# BoostRegulator.net
KiCad netlist of a schematic drawn in Altium Designer
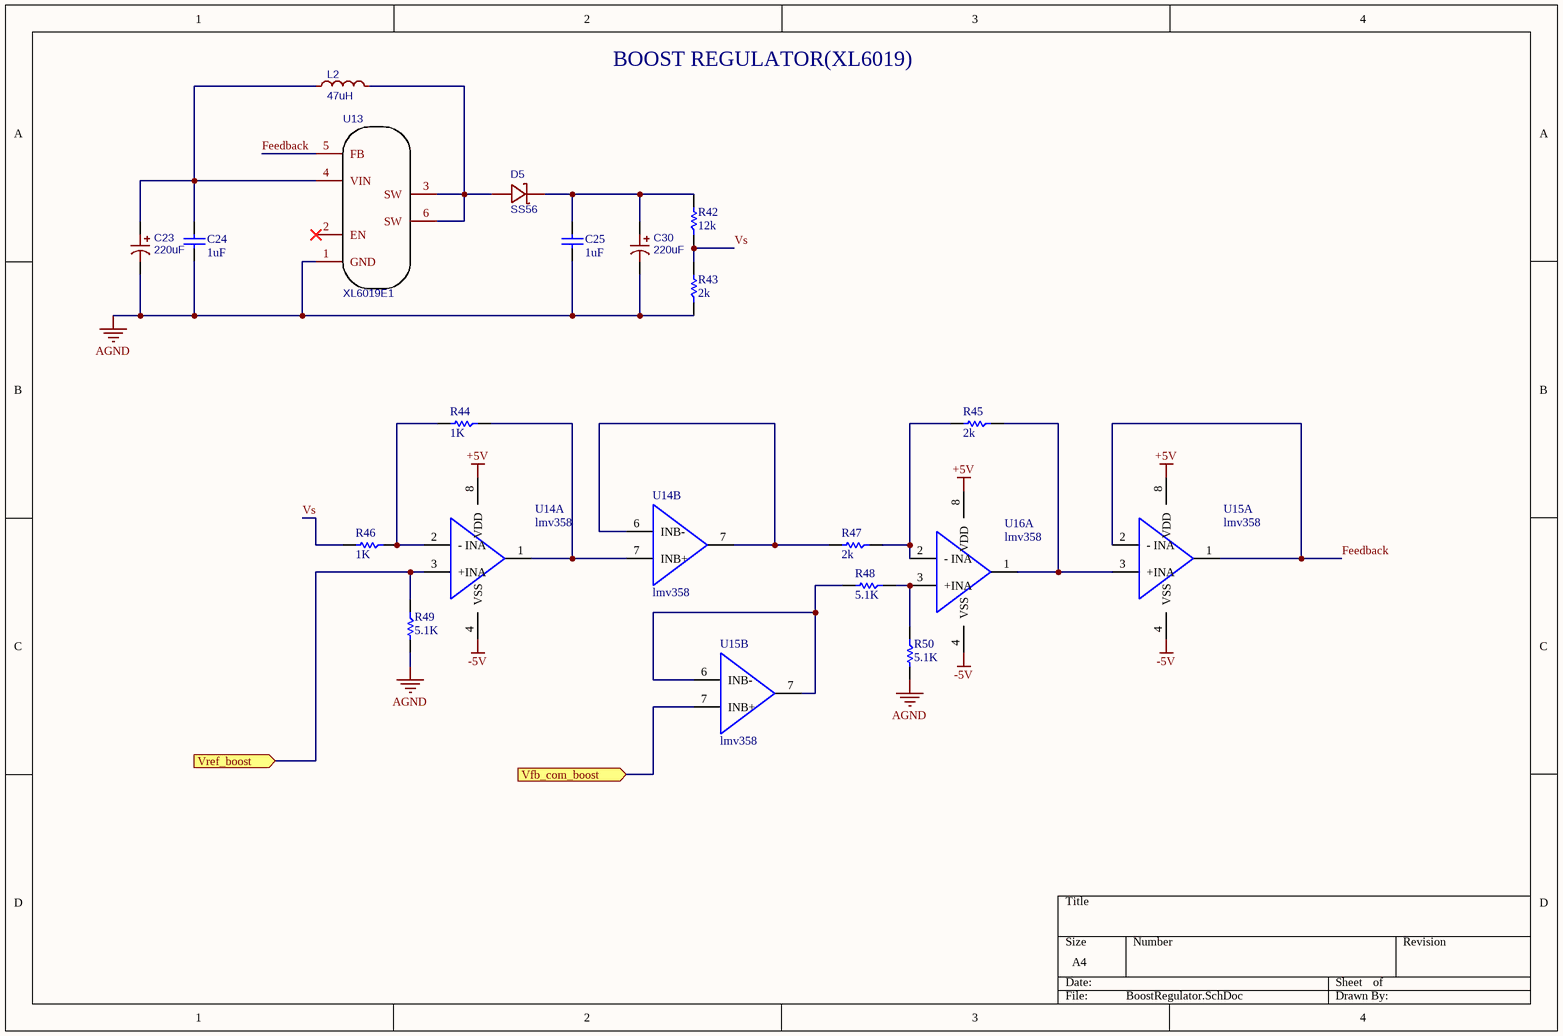
[diagram p0: BoostRegulator.SchDoc]

(export (version "E")
  (design (tool "Eeschema 10.0.6"))
  (components
    (comp (ref "C23")
      (value "220uF")
      (footprint "CAP-SMD_BD10.0-L10.3-W10.3-LS11.0-FD")
      (fields
        (field (name "BOM_SUPPLIER PART") "C2887271")
        (field (name "BOM_MANUFACTURER PART") "RVT220UF50V67RV0021")
        (field (name "CONTRIBUTOR") "LCSC")
      )
      (libsource (lib "Portable power supply") (part "220uF"))
    )
    (comp (ref "C24")
      (value "1uF")
      (footprint "0805C")
      (description "Capacitor")
      (fields (field (name "REVIEWED BY") "RM - 2018/08/05"))
      (libsource (lib "Portable power supply") (part "C_1uf"))
    )
    (comp (ref "C25")
      (value "1uF")
      (footprint "0805C")
      (description "Capacitor")
      (fields (field (name "REVIEWED BY") "RM - 2018/08/05"))
      (libsource (lib "Portable power supply") (part "C_1uf"))
    )
    (comp (ref "C30")
      (value "220uF")
      (footprint "CAP-SMD_BD10.0-L10.3-W10.3-LS11.0-FD")
      (fields
        (field (name "BOM_SUPPLIER PART") "C2887271")
        (field (name "BOM_MANUFACTURER PART") "RVT220UF50V67RV0021")
        (field (name "CONTRIBUTOR") "LCSC")
      )
      (libsource (lib "Portable power supply") (part "220uF"))
    )
    (comp (ref "D5")
      (value "SS56")
      (footprint "SMA_L4.3-W2.6-LS5.2-RD")
      (fields (field (name "BOM_SUPPLIER PART") "C65009"))
      (libsource (lib "Portable power supply") (part "SS56"))
    )
    (comp (ref "L2")
      (value "47uH")
      (footprint "IND-SMD_L12.6-W12.6_MCF-13XX")
      (fields
        (field (name "BOM_SUPPLIER PART") "C497913")
        (field (name "BOM_MANUFACTURER PART") "YSPI1365-470M")
        (field (name "CONTRIBUTOR") "LCSC")
      )
      (libsource (lib "Portable power supply") (part "47uH"))
    )
    (comp (ref "R42")
      (value "12k")
      (footprint "0805")
      (description "Resistor")
      (fields (field (name "REVIEWED BY") "RM - 2018/08/05"))
      (libsource (lib "Portable power supply") (part "R_12k"))
    )
    (comp (ref "R43")
      (value "2k")
      (footprint "0805")
      (description "Resistor")
      (fields (field (name "REVIEWED BY") "RM - 2018/08/05"))
      (libsource (lib "Portable power supply") (part "R_2k"))
    )
    (comp (ref "R44")
      (value "1K")
      (footprint "0805")
      (description "Resistor")
      (fields (field (name "REVIEWED BY") "RM - 2018/08/05"))
      (libsource (lib "Portable power supply") (part "R_6"))
    )
    (comp (ref "R45")
      (value "2k")
      (footprint "0805")
      (description "Resistor")
      (fields (field (name "REVIEWED BY") "RM - 2018/08/05"))
      (libsource (lib "Portable power supply") (part "R_3"))
    )
    (comp (ref "R46")
      (value "1K")
      (footprint "0805")
      (description "Resistor")
      (fields (field (name "REVIEWED BY") "RM - 2018/08/05"))
      (libsource (lib "Portable power supply") (part "R_6"))
    )
    (comp (ref "R47")
      (value "2k")
      (footprint "0805")
      (description "Resistor")
      (fields (field (name "REVIEWED BY") "RM - 2018/08/05"))
      (libsource (lib "Portable power supply") (part "R_3"))
    )
    (comp (ref "R48")
      (value "5.1K")
      (footprint "0805")
      (description "Resistor")
      (fields (field (name "REVIEWED BY") "RM - 2018/08/05"))
      (libsource (lib "Portable power supply") (part "R_1"))
    )
    (comp (ref "R49")
      (value "5.1K")
      (footprint "0805")
      (description "Resistor")
      (fields (field (name "REVIEWED BY") "RM - 2018/08/05"))
      (libsource (lib "Portable power supply") (part "R_1"))
    )
    (comp (ref "R50")
      (value "5.1K")
      (footprint "0805")
      (description "Resistor")
      (fields (field (name "REVIEWED BY") "RM - 2018/08/05"))
      (libsource (lib "Portable power supply") (part "R_1"))
    )
    (comp (ref "U13")
      (value "XL6019E1")
      (footprint "TO-263-5_L10.2-W9.9-P1.70-LS14.4-TL")
      (fields (field (name "BOM_SUPPLIER PART") "C73018"))
      (libsource (lib "Portable power supply") (part "XL6019E1"))
    )
    (comp (ref "U14")
      (value "lmv358")
      (footprint "SOP-8_L4.9-W3.9-P1.27-LS6.0-BL")
      (description "OpAmp High Frequency Dual")
      (fields (field (name "REVIEWED BY") "RM - 2018/08/05"))
      (libsource (lib "Portable power supply") (part "LMV358-SR"))
    )
    (comp (ref "U15")
      (value "lmv358")
      (footprint "SOP-8_L4.9-W3.9-P1.27-LS6.0-BL")
      (description "OpAmp High Frequency Dual")
      (fields (field (name "REVIEWED BY") "RM - 2018/08/05"))
      (libsource (lib "Portable power supply") (part "LMV358-SR"))
    )
    (comp (ref "U16")
      (value "lmv358")
      (footprint "SOP-8_L4.9-W3.9-P1.27-LS6.0-BL")
      (description "OpAmp High Frequency Dual")
      (fields (field (name "REVIEWED BY") "RM - 2018/08/05"))
      (libsource (lib "Portable power supply") (part "LMV358-SR"))
    )
  )
  (nets
    (net (code "1") (name "+5V") (class "Default")
      (node (ref "U14") (pin "8") (pinfunction "VDD_8") (pintype "passive"))
      (node (ref "U15") (pin "8") (pinfunction "VDD_8") (pintype "passive"))
      (node (ref "U16") (pin "8") (pinfunction "VDD_8") (pintype "passive"))
    )
    (net (code "2") (name "-5V") (class "Default")
      (node (ref "U14") (pin "4") (pinfunction "VSS_4") (pintype "passive"))
      (node (ref "U15") (pin "4") (pinfunction "VSS_4") (pintype "passive"))
      (node (ref "U16") (pin "4") (pinfunction "VSS_4") (pintype "passive"))
    )
    (net (code "3") (name "/Feedback") (class "Default")
      (node (ref "U13") (pin "5") (pinfunction "FB_5") (pintype "passive"))
      (node (ref "U15") (pin "1") (pinfunction "OUTA_1") (pintype "passive"))
      (node (ref "U15") (pin "2") (pinfunction "-_INA_2") (pintype "passive"))
    )
    (net (code "4") (name "/Vfb_com_boost") (class "Default")
      (node (ref "U15") (pin "7") (pinfunction "INB+_7") (pintype "passive"))
    )
    (net (code "5") (name "/Vref_boost") (class "Default")
      (node (ref "R49") (pin "1") (pintype "passive"))
      (node (ref "U14") (pin "3") (pinfunction "+INA_3") (pintype "passive"))
    )
    (net (code "6") (name "/Vs") (class "Default")
      (node (ref "R42") (pin "1") (pintype "passive"))
      (node (ref "R43") (pin "2") (pintype "passive"))
      (node (ref "R46") (pin "2") (pintype "passive"))
    )
    (net (code "7") (name "AGND") (class "Default")
      (node (ref "C23") (pin "2") (pinfunction "2_2") (pintype "passive"))
      (node (ref "C24") (pin "2") (pinfunction "2_2") (pintype "passive"))
      (node (ref "C25") (pin "2") (pinfunction "2_2") (pintype "passive"))
      (node (ref "C30") (pin "2") (pinfunction "2_2") (pintype "passive"))
      (node (ref "R43") (pin "1") (pintype "passive"))
      (node (ref "R49") (pin "2") (pintype "passive"))
      (node (ref "R50") (pin "2") (pintype "passive"))
      (node (ref "U13") (pin "1") (pinfunction "GND_1") (pintype "passive"))
    )
    (net (code "8") (name "Net-(D5-A)") (class "Default")
      (node (ref "D5") (pin "2") (pinfunction "A_2") (pintype "passive"))
      (node (ref "L2") (pin "2") (pinfunction "2_2") (pintype "passive"))
      (node (ref "U13") (pin "3") (pinfunction "SW_3") (pintype "passive"))
      (node (ref "U13") (pin "6") (pinfunction "SW_6") (pintype "passive"))
    )
    (net (code "9") (name "Net-(D5-K)") (class "Default")
      (node (ref "C25") (pin "1") (pinfunction "1_1") (pintype "passive"))
      (node (ref "C30") (pin "1") (pinfunction "1_1") (pintype "passive"))
      (node (ref "D5") (pin "1") (pinfunction "K_1") (pintype "passive"))
      (node (ref "R42") (pin "2") (pintype "passive"))
    )
    (net (code "10") (name "Net-(U13-VIN)") (class "Default")
      (node (ref "C23") (pin "1") (pinfunction "1_1") (pintype "passive"))
      (node (ref "C24") (pin "1") (pinfunction "1_1") (pintype "passive"))
      (node (ref "L2") (pin "1") (pinfunction "1_1") (pintype "passive"))
      (node (ref "U13") (pin "4") (pinfunction "VIN_4") (pintype "passive"))
    )
    (net (code "11") (name "Net-(U14A--_INA)") (class "Default")
      (node (ref "R44") (pin "2") (pintype "passive"))
      (node (ref "R46") (pin "1") (pintype "passive"))
      (node (ref "U14") (pin "2") (pinfunction "-_INA_2") (pintype "passive"))
    )
    (net (code "12") (name "Net-(U14A-OUTA)") (class "Default")
      (node (ref "R44") (pin "1") (pintype "passive"))
      (node (ref "U14") (pin "1") (pinfunction "OUTA_1") (pintype "passive"))
      (node (ref "U14") (pin "7") (pinfunction "INB+_7") (pintype "passive"))
    )
    (net (code "13") (name "Net-(U14B-INB-)") (class "Default")
      (node (ref "R47") (pin "2") (pintype "passive"))
      (node (ref "U14") (pin "6") (pinfunction "INB-_6") (pintype "passive"))
      (node (ref "U14") (pin "7") (pinfunction "OUTB_7") (pintype "passive"))
    )
    (net (code "14") (name "Net-(U15A-+INA)") (class "Default")
      (node (ref "R45") (pin "1") (pintype "passive"))
      (node (ref "U15") (pin "3") (pinfunction "+INA_3") (pintype "passive"))
      (node (ref "U16") (pin "1") (pinfunction "OUTA_1") (pintype "passive"))
    )
    (net (code "15") (name "Net-(U15B-INB-)") (class "Default")
      (node (ref "R48") (pin "2") (pintype "passive"))
      (node (ref "U15") (pin "6") (pinfunction "INB-_6") (pintype "passive"))
      (node (ref "U15") (pin "7") (pinfunction "OUTB_7") (pintype "passive"))
    )
    (net (code "16") (name "Net-(U16A-+INA)") (class "Default")
      (node (ref "R48") (pin "1") (pintype "passive"))
      (node (ref "R50") (pin "1") (pintype "passive"))
      (node (ref "U16") (pin "3") (pinfunction "+INA_3") (pintype "passive"))
    )
    (net (code "17") (name "Net-(U16A--_INA)") (class "Default")
      (node (ref "R45") (pin "2") (pintype "passive"))
      (node (ref "R47") (pin "1") (pintype "passive"))
      (node (ref "U16") (pin "2") (pinfunction "-_INA_2") (pintype "passive"))
    )
    (net (code "18") (name "unconnected-(U13-EN-Pad2)") (class "Default")
      (node (ref "U13") (pin "2") (pinfunction "EN_2") (pintype "passive+no_connect"))
    )
  )
)
